# 5_Wzmacniacz_Integrator.net
KiCad netlist of a schematic drawn in Altium Designer
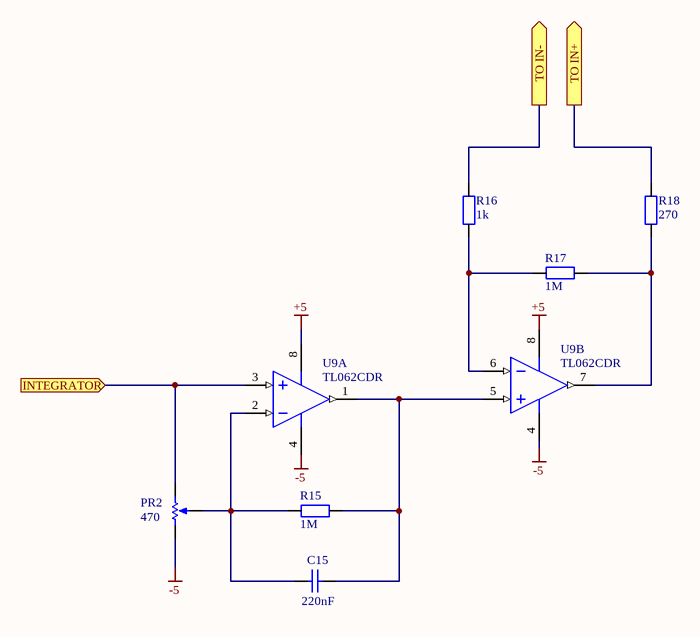
[diagram p0: 5_Wzmacniacz+Integrator.SchDoc]

(export (version "E")
  (design (tool "Eeschema 10.0.6"))
  (components
    (comp (ref "C15")
      (value "CM-220N@TME")
      (footprint "KEMT-C315-THT-2")
      (description "Model: C315C220K1G5TA")
      (fields (field (name "CAPACITANCE") "220nF"))
      (libsource (lib "Altium Content Vault") (part "CAP-NP-2"))
    )
    (comp (ref "PR2")
      (value "T910W-50R@TME")
      (footprint "BOUR-3296W")
      (fields (field (name "RESISTANCE") "470") (field (name "TOLERANCE") "1%"))
      (libsource (lib "Altium Content Vault") (part "RES-POT-3"))
    )
    (comp (ref "R15")
      (value "1M")
      (footprint "R1206")
      (description "Resistor")
      (fields (field (name "Comment") "1206S4J0105T5E@TME"))
      (libsource (lib "MT_Library") (part "Res"))
    )
    (comp (ref "R16")
      (value "1k")
      (footprint "R1206")
      (description "Resistor")
      (fields (field (name "Comment") "1206S4J0102T5E@TME"))
      (libsource (lib "MT_Library") (part "Res"))
    )
    (comp (ref "R17")
      (value "1M")
      (footprint "R1206")
      (description "Resistor")
      (fields (field (name "Comment") "1206S4J0105T5E@TME"))
      (libsource (lib "MT_Library") (part "Res"))
    )
    (comp (ref "R18")
      (value "270")
      (footprint "R1206")
      (description "Resistor")
      (fields (field (name "Comment") "1206S4J0271T5E@TME"))
      (libsource (lib "MT_Library") (part "Res"))
    )
    (comp (ref "U9")
      (value "TL062CDR")
      (footprint "D0008A_N")
      (fields (field (name "MANUFACTURER") "Texas Instruments"))
      (libsource (lib "TL062CDR") (part "CMP-0017-00600-2"))
    )
  )
  (nets
    (net (code "1") (name "+5") (class "Default")
      (node (ref "U9") (pin "8") (pinfunction "VCC+_8") (pintype "power_in"))
    )
    (net (code "2") (name "-5") (class "Default")
      (node (ref "PR2") (pin "1") (pinfunction "CCW_1") (pintype "passive"))
      (node (ref "U9") (pin "4") (pinfunction "VCC-_4") (pintype "power_in"))
    )
    (net (code "3") (name "/INTEGRATOR") (class "Default")
      (node (ref "PR2") (pin "3") (pinfunction "CW_3") (pintype "passive"))
      (node (ref "U9") (pin "3") (pinfunction "IN1+_3") (pintype "input"))
    )
    (net (code "4") (name "/TO IN+") (class "Default")
      (node (ref "R18") (pin "1") (pinfunction "1_1") (pintype "passive"))
    )
    (net (code "5") (name "/TO IN-") (class "Default")
      (node (ref "R16") (pin "1") (pinfunction "1_1") (pintype "passive"))
    )
    (net (code "6") (name "Net-(PR2-S)") (class "Default")
      (node (ref "C15") (pin "1") (pinfunction "1_1") (pintype "passive"))
      (node (ref "PR2") (pin "2") (pinfunction "S_2") (pintype "passive"))
      (node (ref "R15") (pin "1") (pinfunction "1_1") (pintype "passive"))
      (node (ref "U9") (pin "2") (pinfunction "IN1-_2") (pintype "input"))
    )
    (net (code "7") (name "Net-(U9A-OUT1)") (class "Default")
      (node (ref "C15") (pin "2") (pinfunction "2_2") (pintype "passive"))
      (node (ref "R15") (pin "2") (pinfunction "2_2") (pintype "passive"))
      (node (ref "U9") (pin "1") (pinfunction "OUT1_1") (pintype "output"))
      (node (ref "U9") (pin "5") (pinfunction "IN2+_5") (pintype "input"))
    )
    (net (code "8") (name "Net-(U9B-IN2-)") (class "Default")
      (node (ref "R16") (pin "2") (pinfunction "2_2") (pintype "passive"))
      (node (ref "R17") (pin "1") (pinfunction "1_1") (pintype "passive"))
      (node (ref "U9") (pin "6") (pinfunction "IN2-_6") (pintype "input"))
    )
    (net (code "9") (name "Net-(U9B-OUT2)") (class "Default")
      (node (ref "R17") (pin "2") (pinfunction "2_2") (pintype "passive"))
      (node (ref "R18") (pin "2") (pinfunction "2_2") (pintype "passive"))
      (node (ref "U9") (pin "7") (pinfunction "OUT2_7") (pintype "output"))
    )
  )
)
